# USB_PD_Controller.net
KiCad netlist of a schematic drawn in Altium Designer
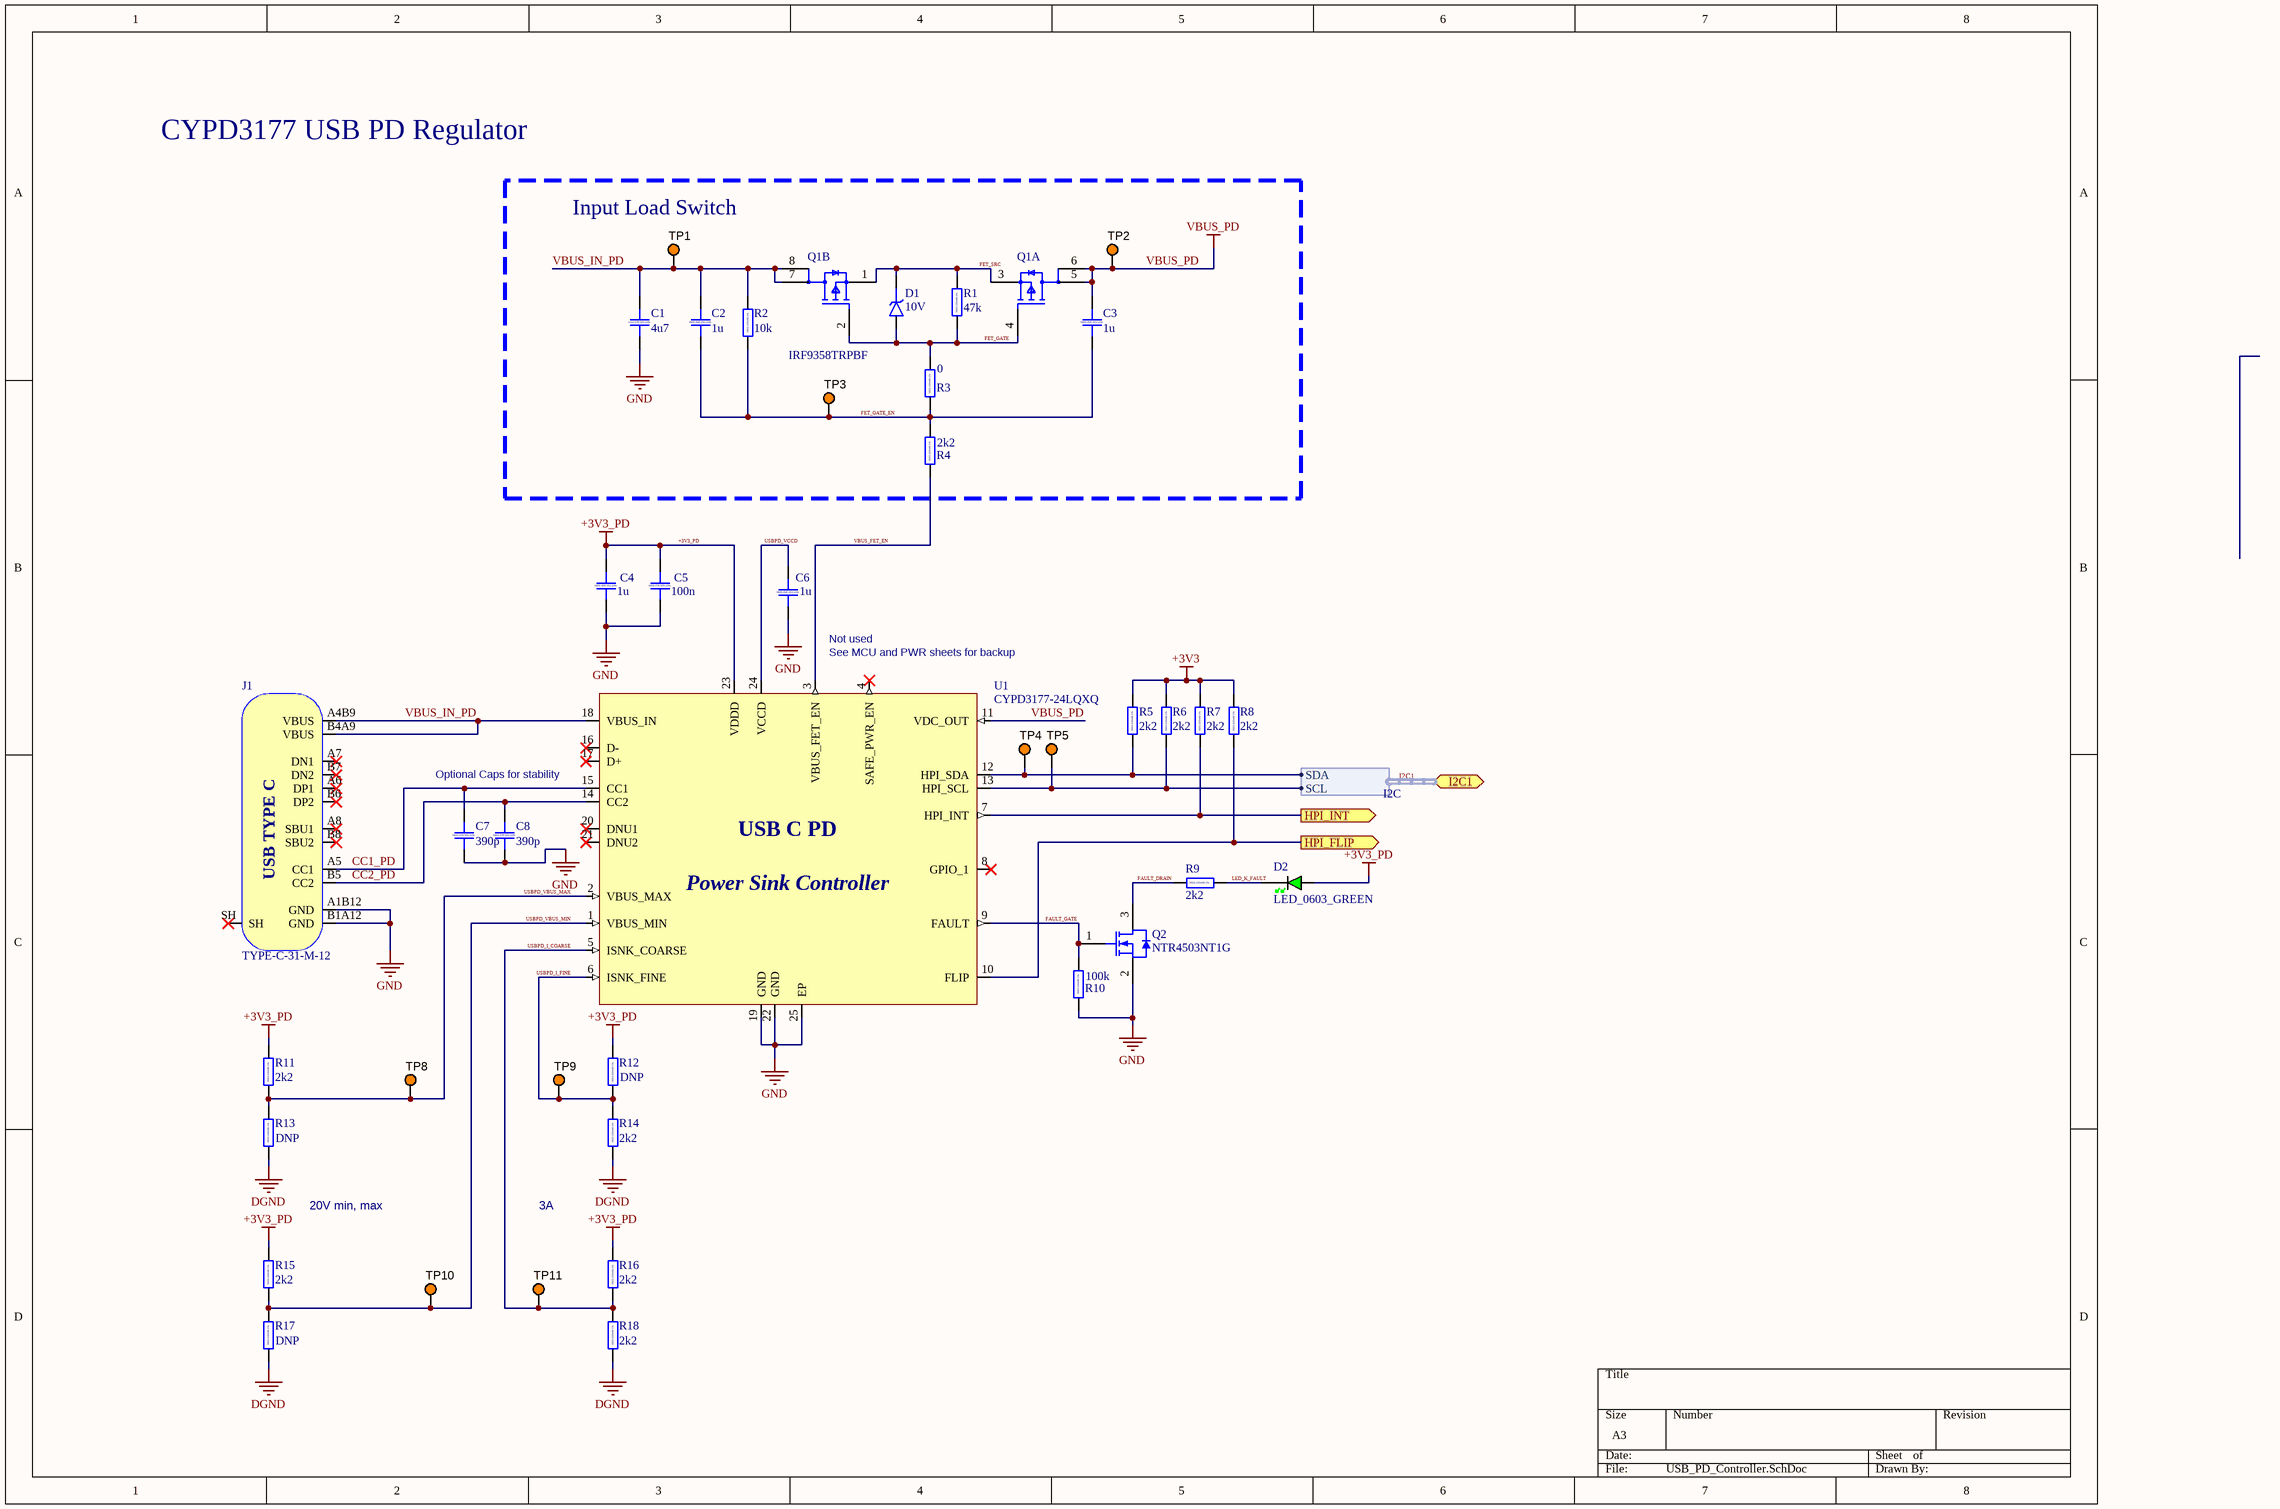
[diagram p0: USB_PD_Controller.SchDoc]

(export (version "E")
  (design (tool "Eeschema 10.0.6"))
  (components
    (comp (ref "C1")
      (value "4u7")
      (footprint "CAP_1210")
      (description "Capacitor SMD 1210")
      (fields (field (name "SOURCE") "Schematic-Lib-PhilsLab.SchLib"))
      (libsource (lib "") (part "CAP_EL_NP_5MM_2"))
    )
    (comp (ref "C2")
      (value "1u")
      (footprint "CAP_0805")
      (description "Capacitor SMD 0805")
      (fields (field (name "SOURCE") "Schematic-Lib-PhilsLab.SchLib"))
      (libsource (lib "") (part "CAP_EL_NP_5MM_1"))
    )
    (comp (ref "C3")
      (value "1u")
      (footprint "CAP_0805")
      (description "Capacitor SMD 0805")
      (fields (field (name "SOURCE") "Schematic-Lib-PhilsLab.SchLib"))
      (libsource (lib "") (part "CAP_EL_NP_5MM_1"))
    )
    (comp (ref "C4")
      (value "1u")
      (footprint "CAP_0805")
      (description "Capacitor SMD 0805")
      (fields (field (name "SOURCE") "Schematic-Lib-PhilsLab.SchLib"))
      (libsource (lib "") (part "CAP_EL_NP_5MM_1"))
    )
    (comp (ref "C5")
      (value "100n")
      (footprint "CAP_0603")
      (description "Capacitor SMD 0603")
      (fields (field (name "SOURCE") "Schematic-Lib-PhilsLab.SchLib"))
      (libsource (lib "Leonhard Waibl") (part "CAP_EL_NP_5MM"))
    )
    (comp (ref "C6")
      (value "1u")
      (footprint "CAP_0805")
      (description "Capacitor SMD 0805")
      (fields (field (name "SOURCE") "Schematic-Lib-PhilsLab.SchLib"))
      (libsource (lib "") (part "CAP_EL_NP_5MM_1"))
    )
    (comp (ref "C7")
      (value "390p")
      (footprint "CAP_0603")
      (description "Capacitor SMD 0603")
      (fields (field (name "SOURCE") "Schematic-Lib-PhilsLab.SchLib"))
      (libsource (lib "Leonhard Waibl") (part "CAP_EL_NP_5MM"))
    )
    (comp (ref "C8")
      (value "390p")
      (footprint "CAP_0603")
      (description "Capacitor SMD 0603")
      (fields (field (name "SOURCE") "Schematic-Lib-PhilsLab.SchLib"))
      (libsource (lib "Leonhard Waibl") (part "CAP_EL_NP_5MM"))
    )
    (comp (ref "D1")
      (value "10V")
      (footprint "SOD-323")
      (description "Diode Zener SMD SOD-323")
      (fields (field (name "SOURCE") "Schematic-Lib-PhilsLab.SchLib"))
      (libsource (lib "Leonhard Waibl") (part "D_ZENER_SOD_323"))
    )
    (comp (ref "D2")
      (value "LED_0603_GREEN")
      (footprint "LED_0603_GREEN")
      (description "LED 0603 GREEN SMD")
      (fields (field (name "SOURCE") "Schematic-Lib-PhilsLab.SchLib"))
      (libsource (lib "Leonhard Waibl") (part "LED_0805_GREEN"))
    )
    (comp (ref "J1")
      (value "TYPE-C-31-M-12")
      (footprint "TYPE-C-31-M-12")
      (description "USB Type C Connector Horizontal SMT")
      (fields
        (field (name "MANUFACTURER") "Koren Hroparts")
        (field (name "SOURCE") "Schematic-Lib-PhilsLab.SchLib")
      )
      (libsource (lib "Leonhard Waibl") (part "TYPE-C-31-M-12"))
    )
    (comp (ref "Q1")
      (value "IRF9358TRPBF")
      (footprint "FP-PG-DSO-8-IPC_A")
      (description "MOSFET 2P-CH 30V 9.2A 8SOIC")
      (libsource (lib "Altium Content Vault") (part "5e38728c795c682e8f1ce7f9b94c653"))
    )
    (comp (ref "Q2")
      (value "NTR4503NT1G")
      (footprint "ONSC-SOT-23-3-318-08_V")
      (description "Power MOSFET, 30 V, 2.5 A, Single N-Channel, 3-Pin SOT-23, Pb-Free, Tape and Reel")
      (fields (field (name "MANUFACTURER") "On Semiconductor"))
      (libsource (lib "Altium Content Vault") (part "ONSC-NMOS-G1S2D3-3"))
    )
    (comp (ref "R1")
      (value "47k")
      (footprint "RES_0603")
      (description "Resistor 0603 100mW 1%")
      (fields (field (name "SOURCE") "Schematic-Lib-PhilsLab.SchLib"))
      (libsource (lib "Leonhard Waibl") (part "RES_5931"))
    )
    (comp (ref "R2")
      (value "10k")
      (footprint "RES_0603")
      (description "Resistor 0603 100mW 1%")
      (fields (field (name "SOURCE") "Schematic-Lib-PhilsLab.SchLib"))
      (libsource (lib "Leonhard Waibl") (part "RES_5931"))
    )
    (comp (ref "R3")
      (value "0")
      (footprint "RES_0603")
      (description "Resistor 0603 100mW 1%")
      (fields (field (name "SOURCE") "Schematic-Lib-PhilsLab.SchLib"))
      (libsource (lib "Leonhard Waibl") (part "RES_5931"))
    )
    (comp (ref "R4")
      (value "2k2")
      (footprint "RES_0603")
      (description "Resistor 0603 100mW 1%")
      (fields (field (name "SOURCE") "Schematic-Lib-PhilsLab.SchLib"))
      (libsource (lib "Leonhard Waibl") (part "RES_5931"))
    )
    (comp (ref "R5")
      (value "2k2")
      (footprint "RES_0603")
      (description "Resistor 0603 100mW 1%")
      (fields (field (name "SOURCE") "Schematic-Lib-PhilsLab.SchLib"))
      (libsource (lib "Leonhard Waibl") (part "RES_5931"))
    )
    (comp (ref "R6")
      (value "2k2")
      (footprint "RES_0603")
      (description "Resistor 0603 100mW 1%")
      (fields (field (name "SOURCE") "Schematic-Lib-PhilsLab.SchLib"))
      (libsource (lib "Leonhard Waibl") (part "RES_5931"))
    )
    (comp (ref "R7")
      (value "2k2")
      (footprint "RES_0603")
      (description "Resistor 0603 100mW 1%")
      (fields (field (name "SOURCE") "Schematic-Lib-PhilsLab.SchLib"))
      (libsource (lib "Leonhard Waibl") (part "RES_5931"))
    )
    (comp (ref "R8")
      (value "2k2")
      (footprint "RES_0603")
      (description "Resistor 0603 100mW 1%")
      (fields (field (name "SOURCE") "Schematic-Lib-PhilsLab.SchLib"))
      (libsource (lib "Leonhard Waibl") (part "RES_5931"))
    )
    (comp (ref "R9")
      (value "2k2")
      (footprint "RES_0603")
      (description "Resistor 0603 100mW 1%")
      (fields (field (name "SOURCE") "Schematic-Lib-PhilsLab.SchLib"))
      (libsource (lib "Leonhard Waibl") (part "RES_5931"))
    )
    (comp (ref "R10")
      (value "100k")
      (footprint "RES_0603")
      (description "Resistor 0603 100mW 1%")
      (fields (field (name "SOURCE") "Schematic-Lib-PhilsLab.SchLib"))
      (libsource (lib "Leonhard Waibl") (part "RES_5931"))
    )
    (comp (ref "R11")
      (value "2k2")
      (footprint "RES_0603")
      (description "Resistor 0603 100mW 1%")
      (fields (field (name "SOURCE") "Schematic-Lib-PhilsLab.SchLib"))
      (libsource (lib "Leonhard Waibl") (part "RES_5931"))
    )
    (comp (ref "R12")
      (value "DNP")
      (footprint "RES_0603")
      (description "Resistor 0603 100mW 1%")
      (fields (field (name "SOURCE") "Schematic-Lib-PhilsLab.SchLib"))
      (libsource (lib "Leonhard Waibl") (part "RES_5931"))
    )
    (comp (ref "R13")
      (value "DNP")
      (footprint "RES_0603")
      (description "Resistor 0603 100mW 1%")
      (fields (field (name "SOURCE") "Schematic-Lib-PhilsLab.SchLib"))
      (libsource (lib "Leonhard Waibl") (part "RES_5931"))
    )
    (comp (ref "R14")
      (value "2k2")
      (footprint "RES_0603")
      (description "Resistor 0603 100mW 1%")
      (fields (field (name "SOURCE") "Schematic-Lib-PhilsLab.SchLib"))
      (libsource (lib "Leonhard Waibl") (part "RES_5931"))
    )
    (comp (ref "R15")
      (value "2k2")
      (footprint "RES_0603")
      (description "Resistor 0603 100mW 1%")
      (fields (field (name "SOURCE") "Schematic-Lib-PhilsLab.SchLib"))
      (libsource (lib "Leonhard Waibl") (part "RES_5931"))
    )
    (comp (ref "R16")
      (value "2k2")
      (footprint "RES_0603")
      (description "Resistor 0603 100mW 1%")
      (fields (field (name "SOURCE") "Schematic-Lib-PhilsLab.SchLib"))
      (libsource (lib "Leonhard Waibl") (part "RES_5931"))
    )
    (comp (ref "R17")
      (value "DNP")
      (footprint "RES_0603")
      (description "Resistor 0603 100mW 1%")
      (fields (field (name "SOURCE") "Schematic-Lib-PhilsLab.SchLib"))
      (libsource (lib "Leonhard Waibl") (part "RES_5931"))
    )
    (comp (ref "R18")
      (value "2k2")
      (footprint "RES_0603")
      (description "Resistor 0603 100mW 1%")
      (fields (field (name "SOURCE") "Schematic-Lib-PhilsLab.SchLib"))
      (libsource (lib "Leonhard Waibl") (part "RES_5931"))
    )
    (comp (ref "TP1")
      (value "5003")
      (footprint "KSTN-5003")
      (description "Test Point, Orange, Height 4.6 mm, Tail Length 3 mm, 1-Pin THD, RoHS")
      (fields (field (name "MANUFACTURER") "Keystone"))
      (libsource (lib "Leonhard Waibl") (part "TESTPOINT_ORANGE"))
    )
    (comp (ref "TP2")
      (value "5003")
      (footprint "KSTN-5003")
      (description "Test Point, Orange, Height 4.6 mm, Tail Length 3 mm, 1-Pin THD, RoHS")
      (fields (field (name "MANUFACTURER") "Keystone"))
      (libsource (lib "Leonhard Waibl") (part "TESTPOINT_ORANGE"))
    )
    (comp (ref "TP3")
      (value "5003")
      (footprint "KSTN-5003")
      (description "Test Point, Orange, Height 4.6 mm, Tail Length 3 mm, 1-Pin THD, RoHS")
      (fields (field (name "MANUFACTURER") "Keystone"))
      (libsource (lib "Leonhard Waibl") (part "TESTPOINT_ORANGE"))
    )
    (comp (ref "TP4")
      (value "5003")
      (footprint "KSTN-5003")
      (description "Test Point, Orange, Height 4.6 mm, Tail Length 3 mm, 1-Pin THD, RoHS")
      (fields (field (name "MANUFACTURER") "Keystone"))
      (libsource (lib "Leonhard Waibl") (part "TESTPOINT_ORANGE"))
    )
    (comp (ref "TP5")
      (value "5003")
      (footprint "KSTN-5003")
      (description "Test Point, Orange, Height 4.6 mm, Tail Length 3 mm, 1-Pin THD, RoHS")
      (fields (field (name "MANUFACTURER") "Keystone"))
      (libsource (lib "Leonhard Waibl") (part "TESTPOINT_ORANGE"))
    )
    (comp (ref "TP8")
      (value "5003")
      (footprint "KSTN-5003")
      (description "Test Point, Orange, Height 4.6 mm, Tail Length 3 mm, 1-Pin THD, RoHS")
      (fields (field (name "MANUFACTURER") "Keystone"))
      (libsource (lib "Leonhard Waibl") (part "TESTPOINT_ORANGE"))
    )
    (comp (ref "TP9")
      (value "5003")
      (footprint "KSTN-5003")
      (description "Test Point, Orange, Height 4.6 mm, Tail Length 3 mm, 1-Pin THD, RoHS")
      (fields (field (name "MANUFACTURER") "Keystone"))
      (libsource (lib "Leonhard Waibl") (part "TESTPOINT_ORANGE"))
    )
    (comp (ref "TP10")
      (value "5003")
      (footprint "KSTN-5003")
      (description "Test Point, Orange, Height 4.6 mm, Tail Length 3 mm, 1-Pin THD, RoHS")
      (fields (field (name "MANUFACTURER") "Keystone"))
      (libsource (lib "Leonhard Waibl") (part "TESTPOINT_ORANGE"))
    )
    (comp (ref "TP11")
      (value "5003")
      (footprint "KSTN-5003")
      (description "Test Point, Orange, Height 4.6 mm, Tail Length 3 mm, 1-Pin THD, RoHS")
      (fields (field (name "MANUFACTURER") "Keystone"))
      (libsource (lib "Leonhard Waibl") (part "TESTPOINT_ORANGE"))
    )
    (comp (ref "U1")
      (value "CYPD3177-24LQXQ")
      (footprint "QFN-24-0MM5")
      (description "USB Type-C Port Controller for Power Sinks")
      (fields
        (field (name "MANUFACTURER") "Cypress Semicon")
        (field (name "SOURCE") "Schematic-Lib-PhilsLab.SchLib")
      )
      (libsource (lib "Leonhard Waibl") (part "CYPD3177-24LQXQ"))
    )
  )
  (nets
    (net (code "2") (name "+3V3") (class "Default")
      (node (ref "R5") (pin "2") (pinfunction "2_2") (pintype "passive"))
      (node (ref "R6") (pin "2") (pinfunction "2_2") (pintype "passive"))
      (node (ref "R7") (pin "2") (pinfunction "2_2") (pintype "passive"))
      (node (ref "R8") (pin "2") (pinfunction "2_2") (pintype "passive"))
    )
    (net (code "3") (name "+3V3_PD") (class "Default")
      (node (ref "C4") (pin "2") (pinfunction "2_2") (pintype "passive"))
      (node (ref "C5") (pin "1") (pinfunction "1_1") (pintype "passive"))
      (node (ref "D2") (pin "A") (pinfunction "A_A") (pintype "passive"))
      (node (ref "R11") (pin "2") (pinfunction "2_2") (pintype "passive"))
      (node (ref "R12") (pin "2") (pinfunction "2_2") (pintype "passive"))
      (node (ref "R15") (pin "2") (pinfunction "2_2") (pintype "passive"))
      (node (ref "R16") (pin "2") (pinfunction "2_2") (pintype "passive"))
      (node (ref "U1") (pin "23") (pinfunction "VDDD_23") (pintype "power_in"))
    )
    (net (code "4") (name "/CC1_PD") (class "Default")
      (node (ref "C7") (pin "1") (pinfunction "1_1") (pintype "passive"))
      (node (ref "J1") (pin "A5") (pinfunction "CC1_A5") (pintype "passive"))
      (node (ref "U1") (pin "15") (pinfunction "CC1_15") (pintype "bidirectional"))
    )
    (net (code "5") (name "/CC2_PD") (class "Default")
      (node (ref "C8") (pin "1") (pinfunction "1_1") (pintype "passive"))
      (node (ref "J1") (pin "B5") (pinfunction "CC2_B5") (pintype "tri_state"))
      (node (ref "U1") (pin "14") (pinfunction "CC2_14") (pintype "bidirectional"))
    )
    (net (code "6") (name "/FAULT_DRAIN") (class "Default")
      (node (ref "Q2") (pin "3") (pinfunction "D_3") (pintype "passive"))
      (node (ref "R9") (pin "1") (pinfunction "1_1") (pintype "passive"))
    )
    (net (code "7") (name "/FAULT_GATE") (class "Default")
      (node (ref "Q2") (pin "1") (pinfunction "G_1") (pintype "passive"))
      (node (ref "R10") (pin "2") (pinfunction "2_2") (pintype "passive"))
      (node (ref "U1") (pin "9") (pinfunction "FAULT_9") (pintype "output"))
    )
    (net (code "8") (name "/FET_GATE") (class "Default")
      (node (ref "D1") (pin "A") (pinfunction "A_A") (pintype "passive"))
      (node (ref "Q1") (pin "2") (pinfunction "G2_2") (pintype "passive"))
      (node (ref "Q1") (pin "4") (pinfunction "G1_4") (pintype "passive"))
      (node (ref "R1") (pin "1") (pinfunction "1_1") (pintype "passive"))
      (node (ref "R3") (pin "2") (pinfunction "2_2") (pintype "passive"))
    )
    (net (code "9") (name "/FET_GATE_EN") (class "Default")
      (node (ref "C2") (pin "1") (pinfunction "1_1") (pintype "passive"))
      (node (ref "C3") (pin "1") (pinfunction "1_1") (pintype "passive"))
      (node (ref "R2") (pin "1") (pinfunction "1_1") (pintype "passive"))
      (node (ref "R3") (pin "1") (pinfunction "1_1") (pintype "passive"))
      (node (ref "R4") (pin "2") (pinfunction "2_2") (pintype "passive"))
      (node (ref "TP3") (pin "1") (pinfunction "1_1") (pintype "passive"))
    )
    (net (code "10") (name "/FET_SRC") (class "Default")
      (node (ref "D1") (pin "K") (pinfunction "K_K") (pintype "passive"))
      (node (ref "Q1") (pin "1") (pinfunction "S2_1") (pintype "passive"))
      (node (ref "Q1") (pin "3") (pinfunction "S1_3") (pintype "passive"))
      (node (ref "R1") (pin "2") (pinfunction "2_2") (pintype "passive"))
    )
    (net (code "11") (name "/HPI_FLIP") (class "Default")
      (node (ref "R8") (pin "1") (pinfunction "1_1") (pintype "passive"))
      (node (ref "U1") (pin "10") (pinfunction "FLIP_10") (pintype "open_collector"))
    )
    (net (code "12") (name "/HPI_INT") (class "Default")
      (node (ref "R7") (pin "1") (pinfunction "1_1") (pintype "passive"))
      (node (ref "U1") (pin "7") (pinfunction "HPI_INT_7") (pintype "output"))
    )
    (net (code "15") (name "/USBPD_I_COARSE") (class "Default")
      (node (ref "R16") (pin "1") (pinfunction "1_1") (pintype "passive"))
      (node (ref "R18") (pin "2") (pinfunction "2_2") (pintype "passive"))
      (node (ref "TP11") (pin "1") (pinfunction "1_1") (pintype "passive"))
      (node (ref "U1") (pin "5") (pinfunction "ISNK_COARSE_5") (pintype "input"))
    )
    (net (code "16") (name "/USBPD_I_FINE") (class "Default")
      (node (ref "R12") (pin "1") (pinfunction "1_1") (pintype "passive"))
      (node (ref "R14") (pin "2") (pinfunction "2_2") (pintype "passive"))
      (node (ref "TP9") (pin "1") (pinfunction "1_1") (pintype "passive"))
      (node (ref "U1") (pin "6") (pinfunction "ISNK_FINE_6") (pintype "input"))
    )
    (net (code "17") (name "/USBPD_VBUS_MAX") (class "Default")
      (node (ref "R11") (pin "1") (pinfunction "1_1") (pintype "passive"))
      (node (ref "R13") (pin "2") (pinfunction "2_2") (pintype "passive"))
      (node (ref "TP8") (pin "1") (pinfunction "1_1") (pintype "passive"))
      (node (ref "U1") (pin "2") (pinfunction "VBUS_MAX_2") (pintype "input"))
    )
    (net (code "18") (name "/USBPD_VBUS_MIN") (class "Default")
      (node (ref "R15") (pin "1") (pinfunction "1_1") (pintype "passive"))
      (node (ref "R17") (pin "2") (pinfunction "2_2") (pintype "passive"))
      (node (ref "TP10") (pin "1") (pinfunction "1_1") (pintype "passive"))
      (node (ref "U1") (pin "1") (pinfunction "VBUS_MIN_1") (pintype "input"))
    )
    (net (code "19") (name "/USBPD_VCCD") (class "Default")
      (node (ref "C6") (pin "2") (pinfunction "2_2") (pintype "passive"))
      (node (ref "U1") (pin "24") (pinfunction "VCCD_24") (pintype "power_in"))
    )
    (net (code "20") (name "/VBUS_FET_EN") (class "Default")
      (node (ref "R4") (pin "1") (pinfunction "1_1") (pintype "passive"))
      (node (ref "U1") (pin "3") (pinfunction "VBUS_FET_EN_3") (pintype "output"))
    )
    (net (code "21") (name "/VBUS_IN_PD") (class "Default")
      (node (ref "C1") (pin "2") (pinfunction "2_2") (pintype "passive"))
      (node (ref "C2") (pin "2") (pinfunction "2_2") (pintype "passive"))
      (node (ref "J1") (pin "A4B9") (pinfunction "VBUS_A4B9") (pintype "power_in"))
      (node (ref "J1") (pin "B4A9") (pinfunction "VBUS_B4A9") (pintype "power_in"))
      (node (ref "Q1") (pin "7") (pinfunction "D2_7") (pintype "passive"))
      (node (ref "Q1") (pin "8") (pinfunction "D2_8") (pintype "passive"))
      (node (ref "R2") (pin "2") (pinfunction "2_2") (pintype "passive"))
      (node (ref "TP1") (pin "1") (pinfunction "1_1") (pintype "passive"))
      (node (ref "U1") (pin "18") (pinfunction "VBUS_IN_18") (pintype "power_in"))
    )
    (net (code "22") (name "DGND") (class "Default")
      (node (ref "R13") (pin "1") (pinfunction "1_1") (pintype "passive"))
      (node (ref "R14") (pin "1") (pinfunction "1_1") (pintype "passive"))
      (node (ref "R17") (pin "1") (pinfunction "1_1") (pintype "passive"))
      (node (ref "R18") (pin "1") (pinfunction "1_1") (pintype "passive"))
    )
    (net (code "23") (name "GND") (class "Default")
      (node (ref "C1") (pin "1") (pinfunction "1_1") (pintype "passive"))
      (node (ref "C4") (pin "1") (pinfunction "1_1") (pintype "passive"))
      (node (ref "C5") (pin "2") (pinfunction "2_2") (pintype "passive"))
      (node (ref "C6") (pin "1") (pinfunction "1_1") (pintype "passive"))
      (node (ref "C7") (pin "2") (pinfunction "2_2") (pintype "passive"))
      (node (ref "C8") (pin "2") (pinfunction "2_2") (pintype "passive"))
      (node (ref "J1") (pin "A1B12") (pinfunction "GND_A1B12") (pintype "power_in"))
      (node (ref "J1") (pin "B1A12") (pinfunction "GND_B1A12") (pintype "power_in"))
      (node (ref "Q2") (pin "2") (pinfunction "S_2") (pintype "passive"))
      (node (ref "R10") (pin "1") (pinfunction "1_1") (pintype "passive"))
      (node (ref "U1") (pin "19") (pinfunction "GND_19") (pintype "power_in"))
      (node (ref "U1") (pin "22") (pinfunction "GND_22") (pintype "power_in"))
      (node (ref "U1") (pin "25") (pinfunction "EP_25") (pintype "power_in"))
    )
    (net (code "24") (name "Net-(D2-PadK)") (class "Default")
      (node (ref "D2") (pin "K") (pinfunction "K_K") (pintype "passive"))
      (node (ref "R9") (pin "2") (pinfunction "2_2") (pintype "passive"))
    )
    (net (code "25") (name "Net-(U1-HPI_SCL)") (class "Default")
      (node (ref "R6") (pin "1") (pinfunction "1_1") (pintype "passive"))
      (node (ref "TP5") (pin "1") (pinfunction "1_1") (pintype "passive"))
      (node (ref "U1") (pin "13") (pinfunction "HPI_SCL_13") (pintype "open_collector"))
    )
    (net (code "26") (name "Net-(U1-HPI_SDA)") (class "Default")
      (node (ref "R5") (pin "1") (pinfunction "1_1") (pintype "passive"))
      (node (ref "TP4") (pin "1") (pinfunction "1_1") (pintype "passive"))
      (node (ref "U1") (pin "12") (pinfunction "HPI_SDA_12") (pintype "open_collector"))
    )
    (net (code "27") (name "VBUS_PD") (class "Default")
      (node (ref "C3") (pin "2") (pinfunction "2_2") (pintype "passive"))
      (node (ref "Q1") (pin "5") (pinfunction "D1_5") (pintype "passive"))
      (node (ref "Q1") (pin "6") (pinfunction "D1_6") (pintype "passive"))
      (node (ref "TP2") (pin "1") (pinfunction "1_1") (pintype "passive"))
      (node (ref "U1") (pin "11") (pinfunction "VDC_OUT_11") (pintype "input"))
    )
    (net (code "28") (name "unconnected-(J1-DN1-PadA7)") (class "Default")
      (node (ref "J1") (pin "A7") (pinfunction "DN1_A7") (pintype "bidirectional+no_connect"))
    )
    (net (code "29") (name "unconnected-(J1-DN2-PadB7)") (class "Default")
      (node (ref "J1") (pin "B7") (pinfunction "DN2_B7") (pintype "bidirectional+no_connect"))
    )
    (net (code "30") (name "unconnected-(J1-DP1-PadA6)") (class "Default")
      (node (ref "J1") (pin "A6") (pinfunction "DP1_A6") (pintype "bidirectional+no_connect"))
    )
    (net (code "31") (name "unconnected-(J1-DP2-PadB6)") (class "Default")
      (node (ref "J1") (pin "B6") (pinfunction "DP2_B6") (pintype "bidirectional+no_connect"))
    )
    (net (code "32") (name "unconnected-(J1-PadSH)") (class "Default")
      (node (ref "J1") (pin "SH") (pinfunction "SH_SH") (pintype "power_in+no_connect"))
    )
    (net (code "33") (name "unconnected-(J1-SBU1-PadA8)") (class "Default")
      (node (ref "J1") (pin "A8") (pinfunction "SBU1_A8") (pintype "bidirectional+no_connect"))
    )
    (net (code "34") (name "unconnected-(J1-SBU2-PadB8)") (class "Default")
      (node (ref "J1") (pin "B8") (pinfunction "SBU2_B8") (pintype "bidirectional+no_connect"))
    )
    (net (code "35") (name "unconnected-(U1-D+-Pad17)") (class "Default")
      (node (ref "U1") (pin "17") (pinfunction "D+_17") (pintype "passive+no_connect"))
    )
    (net (code "36") (name "unconnected-(U1-D--Pad16)") (class "Default")
      (node (ref "U1") (pin "16") (pinfunction "D-_16") (pintype "passive+no_connect"))
    )
    (net (code "37") (name "unconnected-(U1-DNU1-Pad20)") (class "Default")
      (node (ref "U1") (pin "20") (pinfunction "DNU1_20") (pintype "passive+no_connect"))
    )
    (net (code "38") (name "unconnected-(U1-DNU2-Pad21)") (class "Default")
      (node (ref "U1") (pin "21") (pinfunction "DNU2_21") (pintype "passive+no_connect"))
    )
    (net (code "39") (name "unconnected-(U1-GPIO_1-Pad8)") (class "Default")
      (node (ref "U1") (pin "8") (pinfunction "GPIO_1_8") (pintype "bidirectional+no_connect"))
    )
    (net (code "40") (name "unconnected-(U1-SAFE_PWR_EN-Pad4)") (class "Default")
      (node (ref "U1") (pin "4") (pinfunction "SAFE_PWR_EN_4") (pintype "output+no_connect"))
    )
  )
)
